# test_ckt.net
KiCad netlist of a schematic drawn in EAGLE
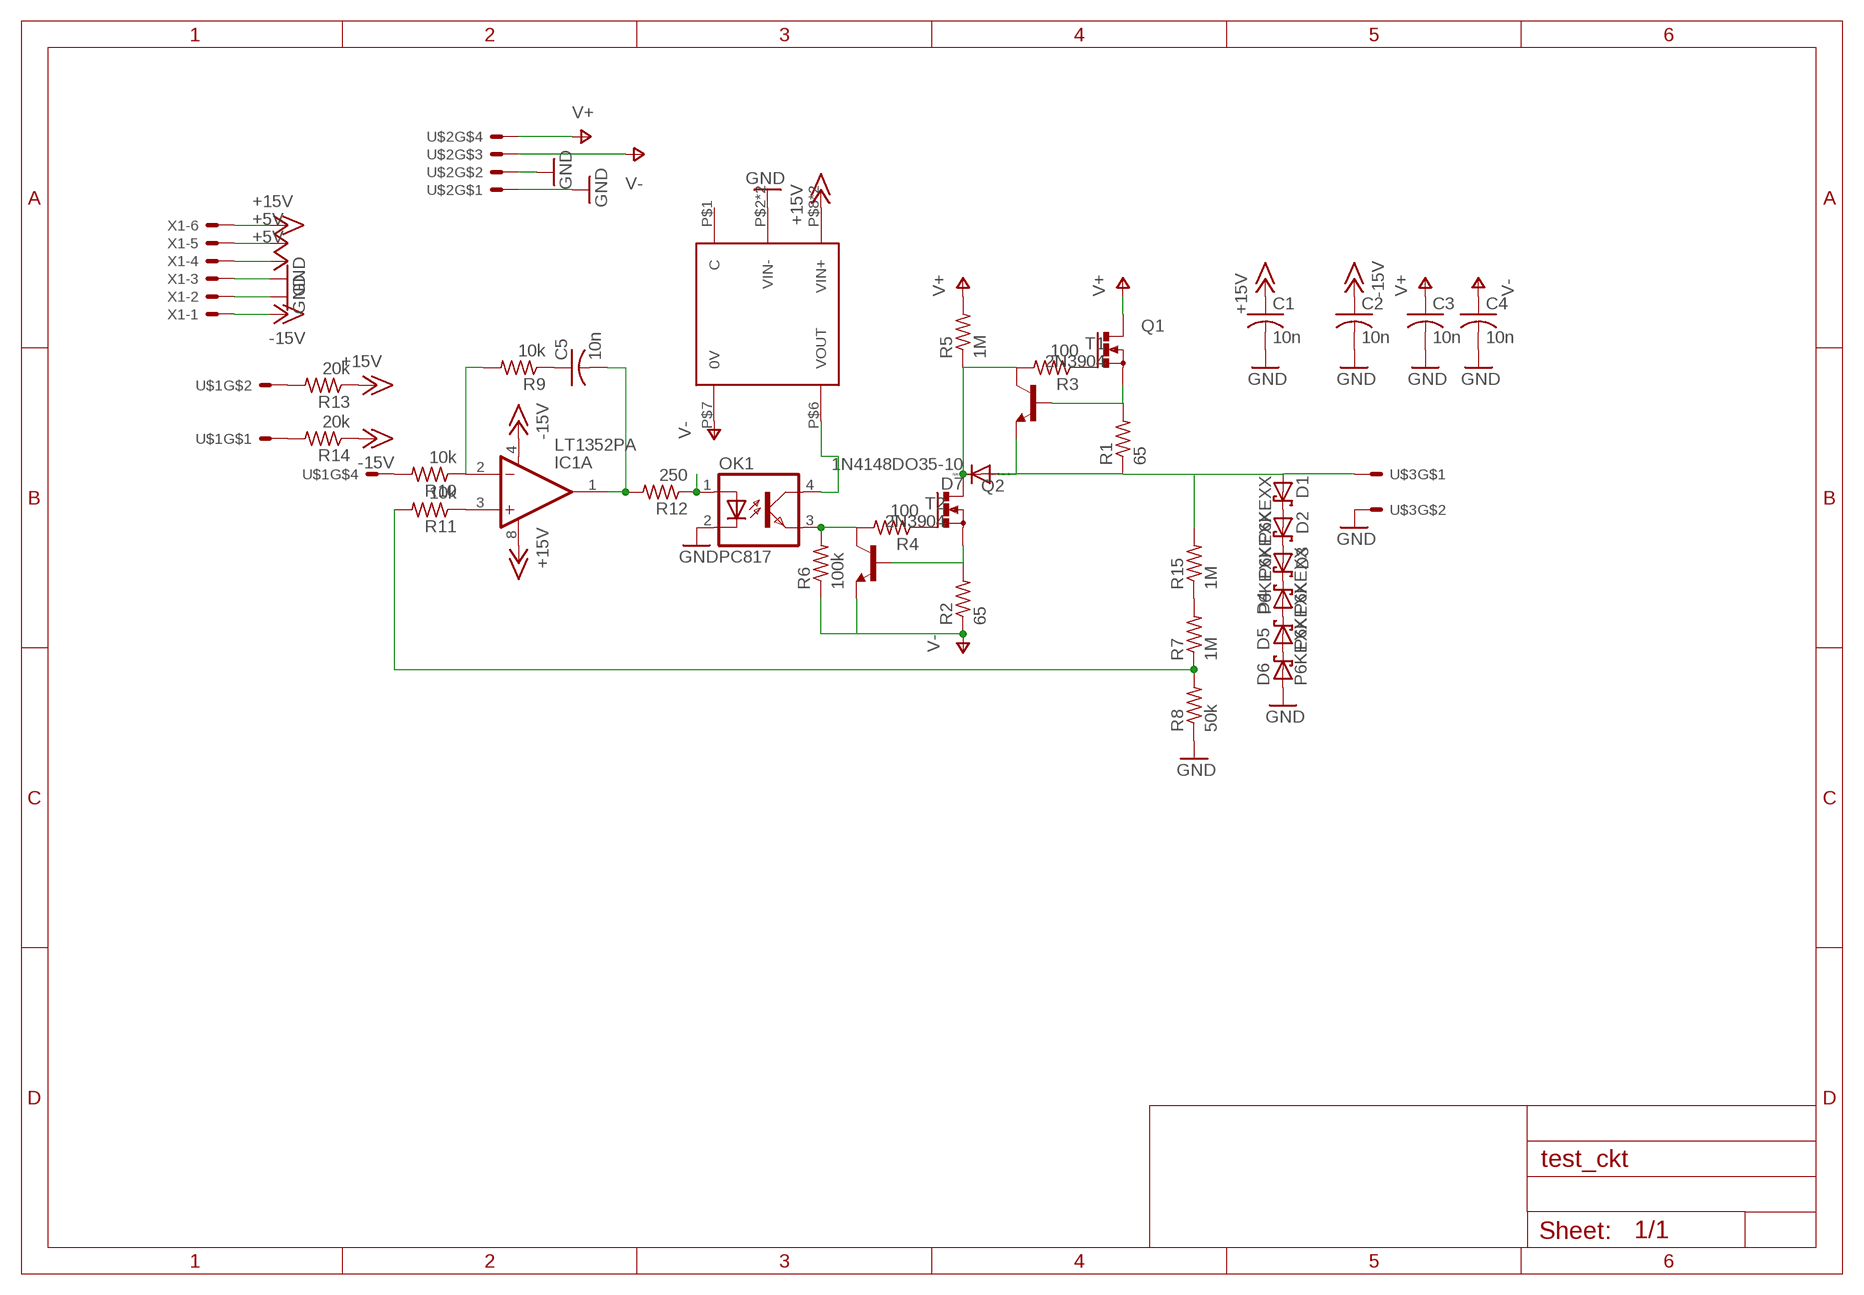
[diagram p0: schematic, sheet 1]

(export (version "E")
  (design (tool "Eeschema 10.0.6"))
  (components
    (comp (ref "C1")
      (value "10n")
      (footprint "eagle-import:C075-032X103")
      (libsource (lib "eagle-import") (part "C-US075-032X103"))
    )
    (comp (ref "C2")
      (value "10n")
      (footprint "eagle-import:C075-032X103")
      (libsource (lib "eagle-import") (part "C-US075-032X103"))
    )
    (comp (ref "C3")
      (value "10n")
      (footprint "eagle-import:C075-032X103")
      (libsource (lib "eagle-import") (part "C-US075-032X103"))
    )
    (comp (ref "C4")
      (value "10n")
      (footprint "eagle-import:C075-032X103")
      (libsource (lib "eagle-import") (part "C-US075-032X103"))
    )
    (comp (ref "C5")
      (value "10n")
      (footprint "eagle-import:C075-032X103")
      (libsource (lib "eagle-import") (part "C-US075-032X103"))
    )
    (comp (ref "D1")
      (value "P6KEXX")
      (footprint "eagle-import:CB417-15")
      (libsource (lib "eagle-import") (part "P6KEXX"))
    )
    (comp (ref "D2")
      (value "P6KEXX")
      (footprint "eagle-import:CB417-15")
      (libsource (lib "eagle-import") (part "P6KEXX"))
    )
    (comp (ref "D3")
      (value "P6KEXX")
      (footprint "eagle-import:CB417-15")
      (libsource (lib "eagle-import") (part "P6KEXX"))
    )
    (comp (ref "D4")
      (value "P6KEXX")
      (footprint "eagle-import:CB417-15")
      (libsource (lib "eagle-import") (part "P6KEXX"))
    )
    (comp (ref "D5")
      (value "P6KEXX")
      (footprint "eagle-import:CB417-15")
      (libsource (lib "eagle-import") (part "P6KEXX"))
    )
    (comp (ref "D6")
      (value "P6KEXX")
      (footprint "eagle-import:CB417-15")
      (libsource (lib "eagle-import") (part "P6KEXX"))
    )
    (comp (ref "D7")
      (value "1N4148DO35-10")
      (footprint "eagle-import:DO35-10")
      (libsource (lib "eagle-import") (part "1N4148DO35-10"))
    )
    (comp (ref "DC1")
      (value "NCS")
      (footprint "eagle-import:NCS")
      (libsource (lib "eagle-import") (part "NCS"))
    )
    (comp (ref "IC1")
      (value "LT1352PA")
      (footprint "eagle-import:DIL08")
      (libsource (lib "eagle-import") (part "LT1352PA"))
    )
    (comp (ref "OK1")
      (value "PC817")
      (footprint "eagle-import:DIL04")
      (fields (field (name "MPN") "PC817X4J000F"))
      (libsource (lib "eagle-import") (part "PC817"))
    )
    (comp (ref "Q1")
      (value "PMOSFET_NTO220BV")
      (footprint "eagle-import:TO220BV")
      (libsource (lib "eagle-import") (part "PMOSFET_NTO220BV"))
    )
    (comp (ref "Q2")
      (value "PMOSFET_NTO220BV")
      (footprint "eagle-import:TO220BV")
      (libsource (lib "eagle-import") (part "PMOSFET_NTO220BV"))
    )
    (comp (ref "R1")
      (value "65")
      (footprint "eagle-import:0207_10")
      (libsource (lib "eagle-import") (part "R-US_0207/10"))
    )
    (comp (ref "R2")
      (value "65")
      (footprint "eagle-import:0207_10")
      (libsource (lib "eagle-import") (part "R-US_0207/10"))
    )
    (comp (ref "R3")
      (value "100")
      (footprint "eagle-import:0207_10")
      (libsource (lib "eagle-import") (part "R-US_0207/10"))
    )
    (comp (ref "R4")
      (value "100")
      (footprint "eagle-import:0207_10")
      (libsource (lib "eagle-import") (part "R-US_0207/10"))
    )
    (comp (ref "R5")
      (value "1M")
      (footprint "eagle-import:0414_15")
      (libsource (lib "eagle-import") (part "resistor_R-US_0414/15"))
    )
    (comp (ref "R6")
      (value "100k")
      (footprint "eagle-import:0207_10")
      (libsource (lib "eagle-import") (part "R-US_0207/10"))
    )
    (comp (ref "R7")
      (value "1M")
      (footprint "eagle-import:0414_15")
      (libsource (lib "eagle-import") (part "resistor_R-US_0414/15"))
    )
    (comp (ref "R8")
      (value "50k")
      (footprint "eagle-import:0207_10")
      (libsource (lib "eagle-import") (part "R-US_0207/10"))
    )
    (comp (ref "R9")
      (value "10k")
      (footprint "eagle-import:0207_10")
      (libsource (lib "eagle-import") (part "R-US_0207/10"))
    )
    (comp (ref "R10")
      (value "10k")
      (footprint "eagle-import:0207_10")
      (libsource (lib "eagle-import") (part "R-US_0207/10"))
    )
    (comp (ref "R11")
      (value "10k")
      (footprint "eagle-import:0207_10")
      (libsource (lib "eagle-import") (part "R-US_0207/10"))
    )
    (comp (ref "R12")
      (value "250")
      (footprint "eagle-import:0207_15")
      (libsource (lib "eagle-import") (part "R-US_0207/15"))
    )
    (comp (ref "R13")
      (value "20k")
      (footprint "eagle-import:0207_10")
      (libsource (lib "eagle-import") (part "R-US_0207/10"))
    )
    (comp (ref "R14")
      (value "20k")
      (footprint "eagle-import:0207_10")
      (libsource (lib "eagle-import") (part "R-US_0207/10"))
    )
    (comp (ref "R15")
      (value "1M")
      (footprint "eagle-import:0414_15")
      (libsource (lib "eagle-import") (part "resistor_R-US_0414/15"))
    )
    (comp (ref "T1")
      (value "2N3904")
      (footprint "eagle-import:TO92")
      (libsource (lib "eagle-import") (part "2N3904"))
    )
    (comp (ref "T2")
      (value "2N3904")
      (footprint "eagle-import:TO92")
      (libsource (lib "eagle-import") (part "2N3904"))
    )
    (comp (ref "U$1")
      (value "5569-4")
      (footprint "eagle-import:5669-4")
      (libsource (lib "eagle-import") (part "5569-4"))
    )
    (comp (ref "U$2")
      (value "5569-4")
      (footprint "eagle-import:5669-4")
      (libsource (lib "eagle-import") (part "5569-4"))
    )
    (comp (ref "U$3")
      (value "5569-2")
      (footprint "eagle-import:5569-2")
      (libsource (lib "eagle-import") (part "5569-2"))
    )
    (comp (ref "X1")
      (value "KK-156-6")
      (footprint "eagle-import:KK-156-6")
      (libsource (lib "eagle-import") (part "KK-156-6"))
    )
  )
  (nets
    (net (code "1") (name "+5V") (class "Default")
      (node (ref "X1") (pin "4") (pinfunction "S_4") (pintype "passive"))
      (node (ref "X1") (pin "5") (pinfunction "S_5") (pintype "passive"))
    )
    (net (code "2") (name "+15V") (class "Default")
      (node (ref "C1") (pin "1") (pinfunction "1_1") (pintype "passive"))
      (node (ref "DC1") (pin "P$8") (pinfunction "VIN+_P$8") (pintype "bidirectional"))
      (node (ref "DC1") (pin "P$9") (pinfunction "VIN+_P$9") (pintype "bidirectional"))
      (node (ref "IC1") (pin "8") (pinfunction "V+_8") (pintype "power_in"))
      (node (ref "R13") (pin "1") (pinfunction "1_1") (pintype "passive"))
      (node (ref "X1") (pin "6") (pinfunction "S_6") (pintype "passive"))
    )
    (net (code "3") (name "-15V") (class "Default")
      (node (ref "C2") (pin "1") (pinfunction "1_1") (pintype "passive"))
      (node (ref "IC1") (pin "4") (pinfunction "V-_4") (pintype "power_in"))
      (node (ref "R14") (pin "1") (pinfunction "1_1") (pintype "passive"))
      (node (ref "X1") (pin "1") (pinfunction "S_1") (pintype "passive"))
    )
    (net (code "4") (name "GND") (class "Default")
      (node (ref "C1") (pin "2") (pinfunction "2_2") (pintype "passive"))
      (node (ref "C2") (pin "2") (pinfunction "2_2") (pintype "passive"))
      (node (ref "C3") (pin "2") (pinfunction "2_2") (pintype "passive"))
      (node (ref "C4") (pin "2") (pinfunction "2_2") (pintype "passive"))
      (node (ref "D6") (pin "A") (pinfunction "A_A") (pintype "passive"))
      (node (ref "DC1") (pin "P$2") (pinfunction "VIN-_P$2") (pintype "bidirectional"))
      (node (ref "DC1") (pin "P$3") (pinfunction "VIN-_P$3") (pintype "bidirectional"))
      (node (ref "OK1") (pin "2") (pinfunction "C_2") (pintype "passive"))
      (node (ref "R8") (pin "1") (pinfunction "1_1") (pintype "passive"))
      (node (ref "U$2") (pin "P$1") (pinfunction "S_P$1") (pintype "passive"))
      (node (ref "U$2") (pin "P$2") (pinfunction "S_P$2") (pintype "passive"))
      (node (ref "U$3") (pin "P$2") (pinfunction "S_P$2") (pintype "passive"))
      (node (ref "X1") (pin "2") (pinfunction "S_2") (pintype "passive"))
      (node (ref "X1") (pin "3") (pinfunction "S_3") (pintype "passive"))
    )
    (net (code "5") (name "Net-(C5-Pad1)") (class "Default")
      (node (ref "C5") (pin "1") (pinfunction "1_1") (pintype "passive"))
      (node (ref "R9") (pin "1") (pinfunction "1_1") (pintype "passive"))
    )
    (net (code "6") (name "Net-(D1-PadC)") (class "Default")
      (node (ref "D1") (pin "C") (pinfunction "C_C") (pintype "passive"))
      (node (ref "D2") (pin "A") (pinfunction "A_A") (pintype "passive"))
    )
    (net (code "7") (name "Net-(D2-PadC)") (class "Default")
      (node (ref "D2") (pin "C") (pinfunction "C_C") (pintype "passive"))
      (node (ref "D3") (pin "A") (pinfunction "A_A") (pintype "passive"))
    )
    (net (code "8") (name "Net-(D3-PadC)") (class "Default")
      (node (ref "D3") (pin "C") (pinfunction "C_C") (pintype "passive"))
      (node (ref "D4") (pin "C") (pinfunction "C_C") (pintype "passive"))
    )
    (net (code "9") (name "Net-(D4-PadA)") (class "Default")
      (node (ref "D4") (pin "A") (pinfunction "A_A") (pintype "passive"))
      (node (ref "D5") (pin "C") (pinfunction "C_C") (pintype "passive"))
    )
    (net (code "10") (name "Net-(D5-PadA)") (class "Default")
      (node (ref "D5") (pin "A") (pinfunction "A_A") (pintype "passive"))
      (node (ref "D6") (pin "C") (pinfunction "C_C") (pintype "passive"))
    )
    (net (code "11") (name "Net-(DC1-VOUT)") (class "Default")
      (node (ref "DC1") (pin "P$6") (pinfunction "VOUT_P$6") (pintype "bidirectional"))
      (node (ref "OK1") (pin "4") (pinfunction "COL_4") (pintype "passive"))
    )
    (net (code "12") (name "Net-(IC1A-+IN)") (class "Default")
      (node (ref "IC1") (pin "3") (pinfunction "+IN_3") (pintype "input"))
      (node (ref "R11") (pin "1") (pinfunction "1_1") (pintype "passive"))
    )
    (net (code "13") (name "Net-(IC1A--IN)") (class "Default")
      (node (ref "IC1") (pin "2") (pinfunction "-IN_2") (pintype "input"))
      (node (ref "R10") (pin "1") (pinfunction "1_1") (pintype "passive"))
      (node (ref "R9") (pin "2") (pinfunction "2_2") (pintype "passive"))
    )
    (net (code "14") (name "Net-(IC1A-OUT)") (class "Default")
      (node (ref "C5") (pin "2") (pinfunction "2_2") (pintype "passive"))
      (node (ref "IC1") (pin "1") (pinfunction "OUT_1") (pintype "output"))
      (node (ref "R12") (pin "2") (pinfunction "2_2") (pintype "passive"))
    )
    (net (code "15") (name "Net-(OK1-A)") (class "Default")
      (node (ref "OK1") (pin "1") (pinfunction "A_1") (pintype "passive"))
      (node (ref "R12") (pin "1") (pinfunction "1_1") (pintype "passive"))
    )
    (net (code "16") (name "Net-(OK1-EMIT)") (class "Default")
      (node (ref "OK1") (pin "3") (pinfunction "EMIT_3") (pintype "passive"))
      (node (ref "R4") (pin "2") (pinfunction "2_2") (pintype "passive"))
      (node (ref "R6") (pin "2") (pinfunction "2_2") (pintype "passive"))
      (node (ref "T2") (pin "1") (pinfunction "C_1") (pintype "passive"))
    )
    (net (code "17") (name "Net-(Q1-PadG)") (class "Default")
      (node (ref "Q1") (pin "G") (pinfunction "G_G") (pintype "passive"))
      (node (ref "R3") (pin "1") (pinfunction "1_1") (pintype "passive"))
    )
    (net (code "18") (name "Net-(Q2-PadG)") (class "Default")
      (node (ref "Q2") (pin "G") (pinfunction "G_G") (pintype "passive"))
      (node (ref "R4") (pin "1") (pinfunction "1_1") (pintype "passive"))
    )
    (net (code "19") (name "Net-(R11-Pad2)") (class "Default")
      (node (ref "R11") (pin "2") (pinfunction "2_2") (pintype "passive"))
      (node (ref "R7") (pin "1") (pinfunction "1_1") (pintype "passive"))
      (node (ref "R8") (pin "2") (pinfunction "2_2") (pintype "passive"))
    )
    (net (code "20") (name "Net-(R15-Pad1)") (class "Default")
      (node (ref "R15") (pin "1") (pinfunction "1_1") (pintype "passive"))
      (node (ref "R7") (pin "2") (pinfunction "2_2") (pintype "passive"))
    )
    (net (code "21") (name "Net-(T1-B)") (class "Default")
      (node (ref "Q1") (pin "S") (pinfunction "S_S") (pintype "passive"))
      (node (ref "R1") (pin "2") (pinfunction "2_2") (pintype "passive"))
      (node (ref "T1") (pin "2") (pinfunction "B_2") (pintype "passive"))
    )
    (net (code "22") (name "Net-(T1-C)") (class "Default")
      (node (ref "D7") (pin "C") (pinfunction "C_C") (pintype "passive"))
      (node (ref "Q2") (pin "D") (pinfunction "D_D") (pintype "passive"))
      (node (ref "R3") (pin "2") (pinfunction "2_2") (pintype "passive"))
      (node (ref "R5") (pin "1") (pinfunction "1_1") (pintype "passive"))
      (node (ref "T1") (pin "1") (pinfunction "C_1") (pintype "passive"))
    )
    (net (code "23") (name "Net-(T1-E)") (class "Default")
      (node (ref "D1") (pin "A") (pinfunction "A_A") (pintype "passive"))
      (node (ref "D7") (pin "A") (pinfunction "A_A") (pintype "passive"))
      (node (ref "R1") (pin "1") (pinfunction "1_1") (pintype "passive"))
      (node (ref "R15") (pin "2") (pinfunction "2_2") (pintype "passive"))
      (node (ref "T1") (pin "3") (pinfunction "E_3") (pintype "passive"))
      (node (ref "U$3") (pin "P$1") (pinfunction "S_P$1") (pintype "passive"))
    )
    (net (code "24") (name "Net-(T2-B)") (class "Default")
      (node (ref "Q2") (pin "S") (pinfunction "S_S") (pintype "passive"))
      (node (ref "R2") (pin "2") (pinfunction "2_2") (pintype "passive"))
      (node (ref "T2") (pin "2") (pinfunction "B_2") (pintype "passive"))
    )
    (net (code "25") (name "Net-(U$1A-S)") (class "Default")
      (node (ref "R14") (pin "2") (pinfunction "2_2") (pintype "passive"))
      (node (ref "U$1") (pin "P$1") (pinfunction "S_P$1") (pintype "passive"))
    )
    (net (code "26") (name "Net-(U$1B-S)") (class "Default")
      (node (ref "R13") (pin "2") (pinfunction "2_2") (pintype "passive"))
      (node (ref "U$1") (pin "P$2") (pinfunction "S_P$2") (pintype "passive"))
    )
    (net (code "27") (name "Net-(U$1D-S)") (class "Default")
      (node (ref "R10") (pin "2") (pinfunction "2_2") (pintype "passive"))
      (node (ref "U$1") (pin "P$4") (pinfunction "S_P$4") (pintype "passive"))
    )
    (net (code "28") (name "V+") (class "Default")
      (node (ref "C3") (pin "1") (pinfunction "1_1") (pintype "passive"))
      (node (ref "Q1") (pin "D") (pinfunction "D_D") (pintype "passive"))
      (node (ref "R5") (pin "2") (pinfunction "2_2") (pintype "passive"))
      (node (ref "U$2") (pin "P$4") (pinfunction "S_P$4") (pintype "passive"))
    )
    (net (code "29") (name "V-") (class "Default")
      (node (ref "C4") (pin "1") (pinfunction "1_1") (pintype "passive"))
      (node (ref "DC1") (pin "P$7") (pinfunction "0V_P$7") (pintype "bidirectional"))
      (node (ref "R2") (pin "1") (pinfunction "1_1") (pintype "passive"))
      (node (ref "R6") (pin "1") (pinfunction "1_1") (pintype "passive"))
      (node (ref "T2") (pin "3") (pinfunction "E_3") (pintype "passive"))
      (node (ref "U$2") (pin "P$3") (pinfunction "S_P$3") (pintype "passive"))
    )
    (net (code "30") (name "unconnected-(DC1-C-PadP$1)") (class "Default")
      (node (ref "DC1") (pin "P$1") (pinfunction "C_P$1") (pintype "bidirectional"))
    )
  )
)
